# NSTAP.net
KiCad netlist of a schematic drawn in EAGLE
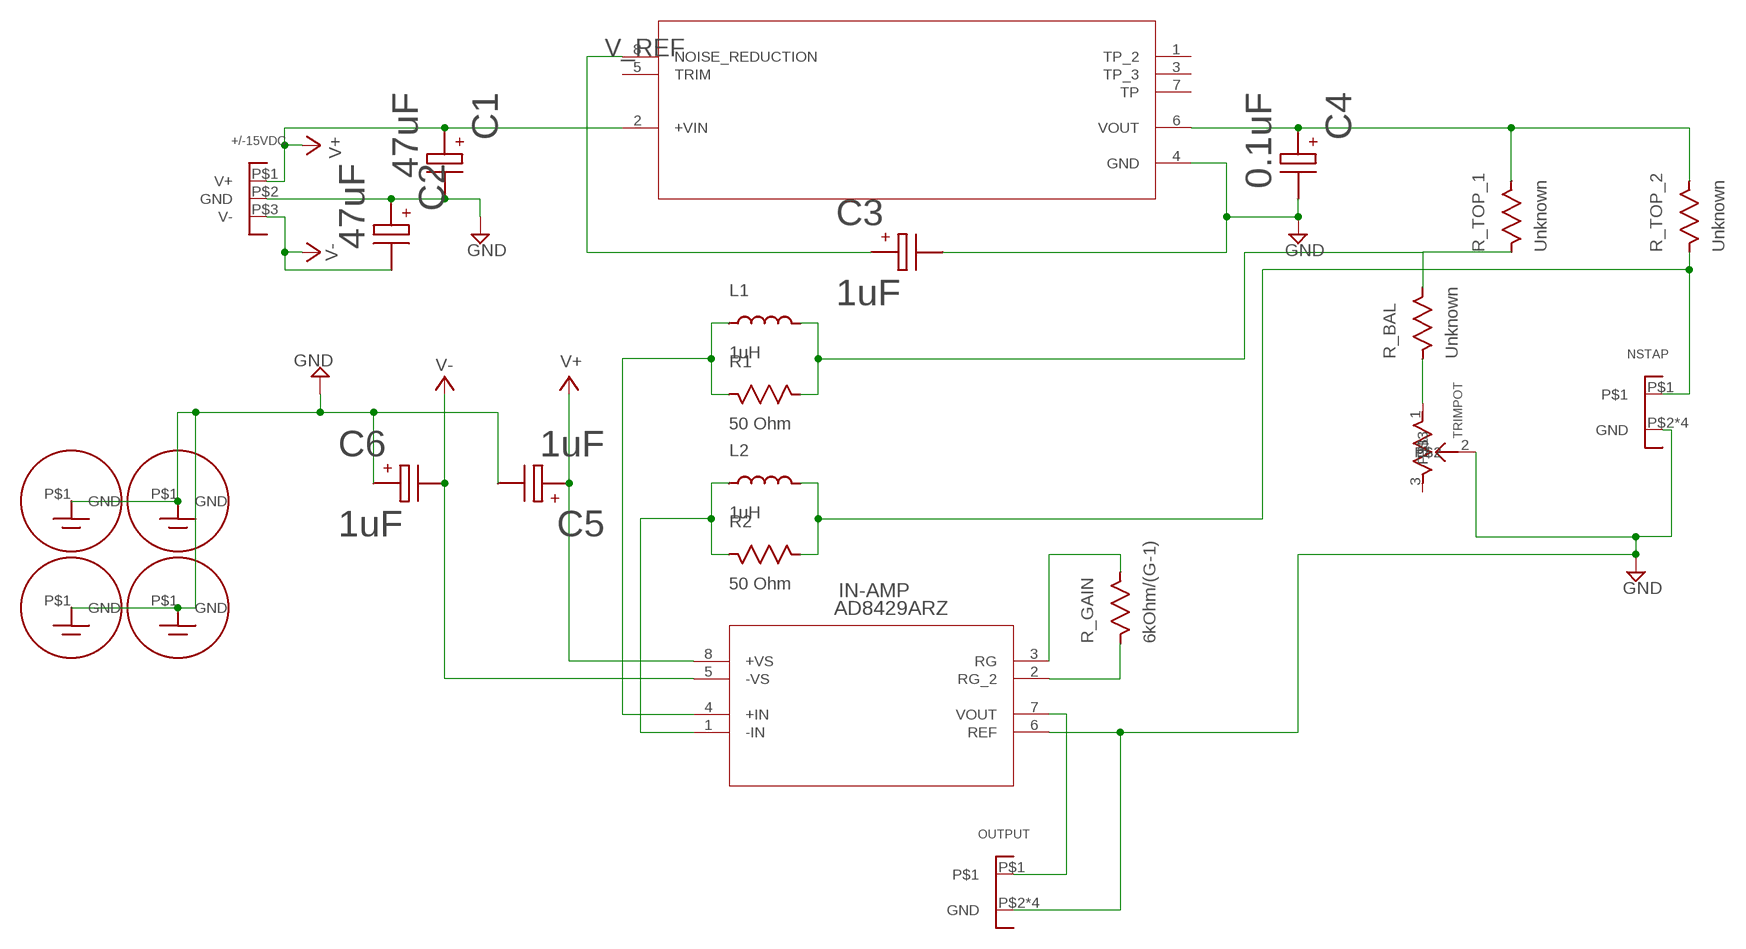
[diagram p0: schematic, sheet 1]

(export (version "E")
  (design (tool "Eeschema 10.0.6"))
  (components
    (comp (ref "+/-15VDC")
      (value "CONNECTOR_3COND\"\"")
      (footprint "eagle-import:SCREW_TERM3X-OST")
      (libsource (lib "eagle-import") (part "CONNECTOR_3COND{dblquote}{dblquote}"))
    )
    (comp (ref "C1")
      (value "47uF")
      (footprint "eagle-import:BRD_0075X050-P")
      (libsource (lib "eagle-import") (part "CAPACITOR_POLARISEDBRD-0075X050"))
    )
    (comp (ref "C2")
      (value "47uF")
      (footprint "eagle-import:BRD_0075X050-P")
      (libsource (lib "eagle-import") (part "CAPACITOR_POLARISEDBRD-0075X050"))
    )
    (comp (ref "C3")
      (value "1uF")
      (footprint "eagle-import:BRD_0075X025-P")
      (libsource (lib "eagle-import") (part "CAPACITOR_POLARISEDBRD-0075X025"))
    )
    (comp (ref "C4")
      (value "0.1uF")
      (footprint "eagle-import:BRD_0075X050-P")
      (libsource (lib "eagle-import") (part "CAPACITOR_POLARISEDBRD-0075X050"))
    )
    (comp (ref "C5")
      (value "1uF")
      (footprint "eagle-import:BRD_0075X025-P")
      (libsource (lib "eagle-import") (part "CAPACITOR_POLARISEDBRD-0075X025"))
    )
    (comp (ref "C6")
      (value "1uF")
      (footprint "eagle-import:BRD_0075X025-P")
      (libsource (lib "eagle-import") (part "CAPACITOR_POLARISEDBRD-0075X025"))
    )
    (comp (ref "IN-AMP")
      (value "AD8429ARZ")
      (footprint "eagle-import:R_8")
      (libsource (lib "eagle-import") (part "AD8429ARZ"))
    )
    (comp (ref "L1")
      (value "1uH")
      (footprint "eagle-import:BRD_0075X150")
      (libsource (lib "eagle-import") (part "INDUCTORBRD-0075X150"))
    )
    (comp (ref "L2")
      (value "1uH")
      (footprint "eagle-import:BRD_0075X150")
      (libsource (lib "eagle-import") (part "INDUCTORBRD-0075X150"))
    )
    (comp (ref "NSTAP")
      (value "CONNECTOR_COAXAMPHENOL-2037")
      (footprint "eagle-import:BNC_AMPHENOL")
      (libsource (lib "eagle-import") (part "CONNECTOR_COAXAMPHENOL-2037"))
    )
    (comp (ref "OUTPUT")
      (value "CONNECTOR_COAXAMPHENOL-2037")
      (footprint "eagle-import:BNC_AMPHENOL")
      (libsource (lib "eagle-import") (part "CONNECTOR_COAXAMPHENOL-2037"))
    )
    (comp (ref "R1")
      (value "50 Ohm")
      (footprint "eagle-import:BRD_0075X100")
      (libsource (lib "eagle-import") (part "RESISTORBRD-0075X100"))
    )
    (comp (ref "R2")
      (value "50 Ohm")
      (footprint "eagle-import:BRD_0075X100")
      (libsource (lib "eagle-import") (part "RESISTORBRD-0075X100"))
    )
    (comp (ref "R_BAL")
      (value "Unknown")
      (footprint "eagle-import:BRD_0075X100")
      (libsource (lib "eagle-import") (part "RESISTORBRD-0075X100"))
    )
    (comp (ref "R_GAIN")
      (value "6kOhm/(G-1)")
      (footprint "eagle-import:BRD_0075X100")
      (libsource (lib "eagle-import") (part "RESISTORBRD-0075X100"))
    )
    (comp (ref "R_TOP_1")
      (value "Unknown")
      (footprint "eagle-import:BRD_0075X100")
      (libsource (lib "eagle-import") (part "RESISTORBRD-0075X100"))
    )
    (comp (ref "R_TOP_2")
      (value "Unknown")
      (footprint "eagle-import:BRD_0075X100")
      (libsource (lib "eagle-import") (part "RESISTORBRD-0075X100"))
    )
    (comp (ref "TRIMPOT")
      (value "TRIM_POT")
      (footprint "eagle-import:TRIM_POT")
      (libsource (lib "eagle-import") (part "TRIM_POT"))
    )
    (comp (ref "U$1")
      (value "GND-SCREW4MM")
      (footprint "eagle-import:GND-SCREW_4MM")
      (libsource (lib "eagle-import") (part "GND-SCREW4MM"))
    )
    (comp (ref "U$2")
      (value "GND-SCREW4MM")
      (footprint "eagle-import:GND-SCREW_4MM")
      (libsource (lib "eagle-import") (part "GND-SCREW4MM"))
    )
    (comp (ref "U$3")
      (value "GND-SCREW4MM")
      (footprint "eagle-import:GND-SCREW_4MM")
      (libsource (lib "eagle-import") (part "GND-SCREW4MM"))
    )
    (comp (ref "U$4")
      (value "GND-SCREW4MM")
      (footprint "eagle-import:GND-SCREW_4MM")
      (libsource (lib "eagle-import") (part "GND-SCREW4MM"))
    )
    (comp (ref "V_REF")
      (value "AD587KNZ")
      (footprint "eagle-import:N_8")
      (libsource (lib "eagle-import") (part "AD587KNZ"))
    )
  )
  (nets
    (net (code "1") (name "GND") (class "Default")
      (node (ref "+/-15VDC") (pin "P$2") (pinfunction "GND_P$2") (pintype "bidirectional"))
      (node (ref "C1") (pin "P$2") (pinfunction "P$2_P$2") (pintype "bidirectional"))
      (node (ref "C2") (pin "P$1") (pinfunction "P$1_P$1") (pintype "bidirectional"))
      (node (ref "C3") (pin "P$2") (pinfunction "P$2_P$2") (pintype "bidirectional"))
      (node (ref "C4") (pin "P$2") (pinfunction "P$2_P$2") (pintype "bidirectional"))
      (node (ref "C5") (pin "P$2") (pinfunction "P$2_P$2") (pintype "bidirectional"))
      (node (ref "C6") (pin "P$1") (pinfunction "P$1_P$1") (pintype "bidirectional"))
      (node (ref "IN-AMP") (pin "6") (pinfunction "REF_6") (pintype "passive"))
      (node (ref "NSTAP") (pin "P$2") (pinfunction "GND_P$2") (pintype "bidirectional"))
      (node (ref "NSTAP") (pin "P$3") (pinfunction "GND_P$3") (pintype "bidirectional"))
      (node (ref "NSTAP") (pin "P$4") (pinfunction "GND_P$4") (pintype "bidirectional"))
      (node (ref "NSTAP") (pin "P$5") (pinfunction "GND_P$5") (pintype "bidirectional"))
      (node (ref "OUTPUT") (pin "P$2") (pinfunction "GND_P$2") (pintype "bidirectional"))
      (node (ref "OUTPUT") (pin "P$3") (pinfunction "GND_P$3") (pintype "bidirectional"))
      (node (ref "OUTPUT") (pin "P$4") (pinfunction "GND_P$4") (pintype "bidirectional"))
      (node (ref "OUTPUT") (pin "P$5") (pinfunction "GND_P$5") (pintype "bidirectional"))
      (node (ref "TRIMPOT") (pin "2") (pinfunction "P$2_2") (pintype "bidirectional"))
      (node (ref "U$1") (pin "P$1") (pinfunction "GND_P$1") (pintype "bidirectional"))
      (node (ref "U$2") (pin "P$1") (pinfunction "GND_P$1") (pintype "bidirectional"))
      (node (ref "U$3") (pin "P$1") (pinfunction "GND_P$1") (pintype "bidirectional"))
      (node (ref "U$4") (pin "P$1") (pinfunction "GND_P$1") (pintype "bidirectional"))
      (node (ref "V_REF") (pin "4") (pinfunction "GND_4") (pintype "passive"))
    )
    (net (code "2") (name "Net-(IN-AMP-+IN)") (class "Default")
      (node (ref "IN-AMP") (pin "4") (pinfunction "+IN_4") (pintype "passive"))
      (node (ref "L1") (pin "P$1") (pinfunction "P$1_P$1") (pintype "bidirectional"))
      (node (ref "R1") (pin "P$1") (pinfunction "P$1_P$1") (pintype "bidirectional"))
    )
    (net (code "3") (name "Net-(IN-AMP--IN)") (class "Default")
      (node (ref "IN-AMP") (pin "1") (pinfunction "-IN_1") (pintype "passive"))
      (node (ref "L2") (pin "P$1") (pinfunction "P$1_P$1") (pintype "bidirectional"))
      (node (ref "R2") (pin "P$1") (pinfunction "P$1_P$1") (pintype "bidirectional"))
    )
    (net (code "4") (name "Net-(IN-AMP-RG)") (class "Default")
      (node (ref "IN-AMP") (pin "3") (pinfunction "RG_3") (pintype "passive"))
      (node (ref "R_GAIN") (pin "P$2") (pinfunction "P$2_P$2") (pintype "bidirectional"))
    )
    (net (code "5") (name "Net-(IN-AMP-RG_2)") (class "Default")
      (node (ref "IN-AMP") (pin "2") (pinfunction "RG_2_2") (pintype "passive"))
      (node (ref "R_GAIN") (pin "P$1") (pinfunction "P$1_P$1") (pintype "bidirectional"))
    )
    (net (code "6") (name "Net-(IN-AMP-VOUT)") (class "Default")
      (node (ref "IN-AMP") (pin "7") (pinfunction "VOUT_7") (pintype "passive"))
      (node (ref "OUTPUT") (pin "P$1") (pinfunction "P$1_P$1") (pintype "bidirectional"))
    )
    (net (code "7") (name "Net-(L1-PadP$2)") (class "Default")
      (node (ref "L1") (pin "P$2") (pinfunction "P$2_P$2") (pintype "bidirectional"))
      (node (ref "R1") (pin "P$2") (pinfunction "P$2_P$2") (pintype "bidirectional"))
      (node (ref "R_BAL") (pin "P$2") (pinfunction "P$2_P$2") (pintype "bidirectional"))
      (node (ref "R_TOP_1") (pin "P$1") (pinfunction "P$1_P$1") (pintype "bidirectional"))
    )
    (net (code "8") (name "Net-(L2-PadP$2)") (class "Default")
      (node (ref "L2") (pin "P$2") (pinfunction "P$2_P$2") (pintype "bidirectional"))
      (node (ref "NSTAP") (pin "P$1") (pinfunction "P$1_P$1") (pintype "bidirectional"))
      (node (ref "R2") (pin "P$2") (pinfunction "P$2_P$2") (pintype "bidirectional"))
      (node (ref "R_TOP_2") (pin "P$1") (pinfunction "P$1_P$1") (pintype "bidirectional"))
    )
    (net (code "9") (name "Net-(TRIMPOT-P$1)") (class "Default")
      (node (ref "R_BAL") (pin "P$1") (pinfunction "P$1_P$1") (pintype "bidirectional"))
      (node (ref "TRIMPOT") (pin "1") (pinfunction "P$1_1") (pintype "bidirectional"))
    )
    (net (code "10") (name "Net-(V_REF-NOISE_REDUCTION)") (class "Default")
      (node (ref "C3") (pin "P$1") (pinfunction "P$1_P$1") (pintype "bidirectional"))
      (node (ref "V_REF") (pin "8") (pinfunction "NOISE_REDUCTION_8") (pintype "passive"))
    )
    (net (code "11") (name "Net-(V_REF-VOUT)") (class "Default")
      (node (ref "C4") (pin "P$1") (pinfunction "P$1_P$1") (pintype "bidirectional"))
      (node (ref "R_TOP_1") (pin "P$2") (pinfunction "P$2_P$2") (pintype "bidirectional"))
      (node (ref "R_TOP_2") (pin "P$2") (pinfunction "P$2_P$2") (pintype "bidirectional"))
      (node (ref "V_REF") (pin "6") (pinfunction "VOUT_6") (pintype "passive"))
    )
    (net (code "12") (name "V+") (class "Default")
      (node (ref "+/-15VDC") (pin "P$1") (pinfunction "V+_P$1") (pintype "bidirectional"))
      (node (ref "C1") (pin "P$1") (pinfunction "P$1_P$1") (pintype "bidirectional"))
      (node (ref "C5") (pin "P$1") (pinfunction "P$1_P$1") (pintype "bidirectional"))
      (node (ref "IN-AMP") (pin "8") (pinfunction "+VS_8") (pintype "passive"))
      (node (ref "V_REF") (pin "2") (pinfunction "+VIN_2") (pintype "passive"))
    )
    (net (code "13") (name "V-") (class "Default")
      (node (ref "+/-15VDC") (pin "P$3") (pinfunction "V-_P$3") (pintype "bidirectional"))
      (node (ref "C2") (pin "P$2") (pinfunction "P$2_P$2") (pintype "bidirectional"))
      (node (ref "C6") (pin "P$2") (pinfunction "P$2_P$2") (pintype "bidirectional"))
      (node (ref "IN-AMP") (pin "5") (pinfunction "-VS_5") (pintype "passive"))
    )
    (net (code "14") (name "unconnected-(TRIMPOT-P$3-Pad3)") (class "Default")
      (node (ref "TRIMPOT") (pin "3") (pinfunction "P$3_3") (pintype "bidirectional"))
    )
    (net (code "15") (name "unconnected-(V_REF-TP-Pad7)") (class "Default")
      (node (ref "V_REF") (pin "7") (pinfunction "TP_7") (pintype "passive"))
    )
    (net (code "16") (name "unconnected-(V_REF-TP_2-Pad1)") (class "Default")
      (node (ref "V_REF") (pin "1") (pinfunction "TP_2_1") (pintype "passive"))
    )
    (net (code "17") (name "unconnected-(V_REF-TP_3-Pad3)") (class "Default")
      (node (ref "V_REF") (pin "3") (pinfunction "TP_3_3") (pintype "passive"))
    )
    (net (code "18") (name "unconnected-(V_REF-TRIM-Pad5)") (class "Default")
      (node (ref "V_REF") (pin "5") (pinfunction "TRIM_5") (pintype "passive"))
    )
  )
)
